# NE555_sample.net
KiCad netlist of a schematic drawn in EAGLE
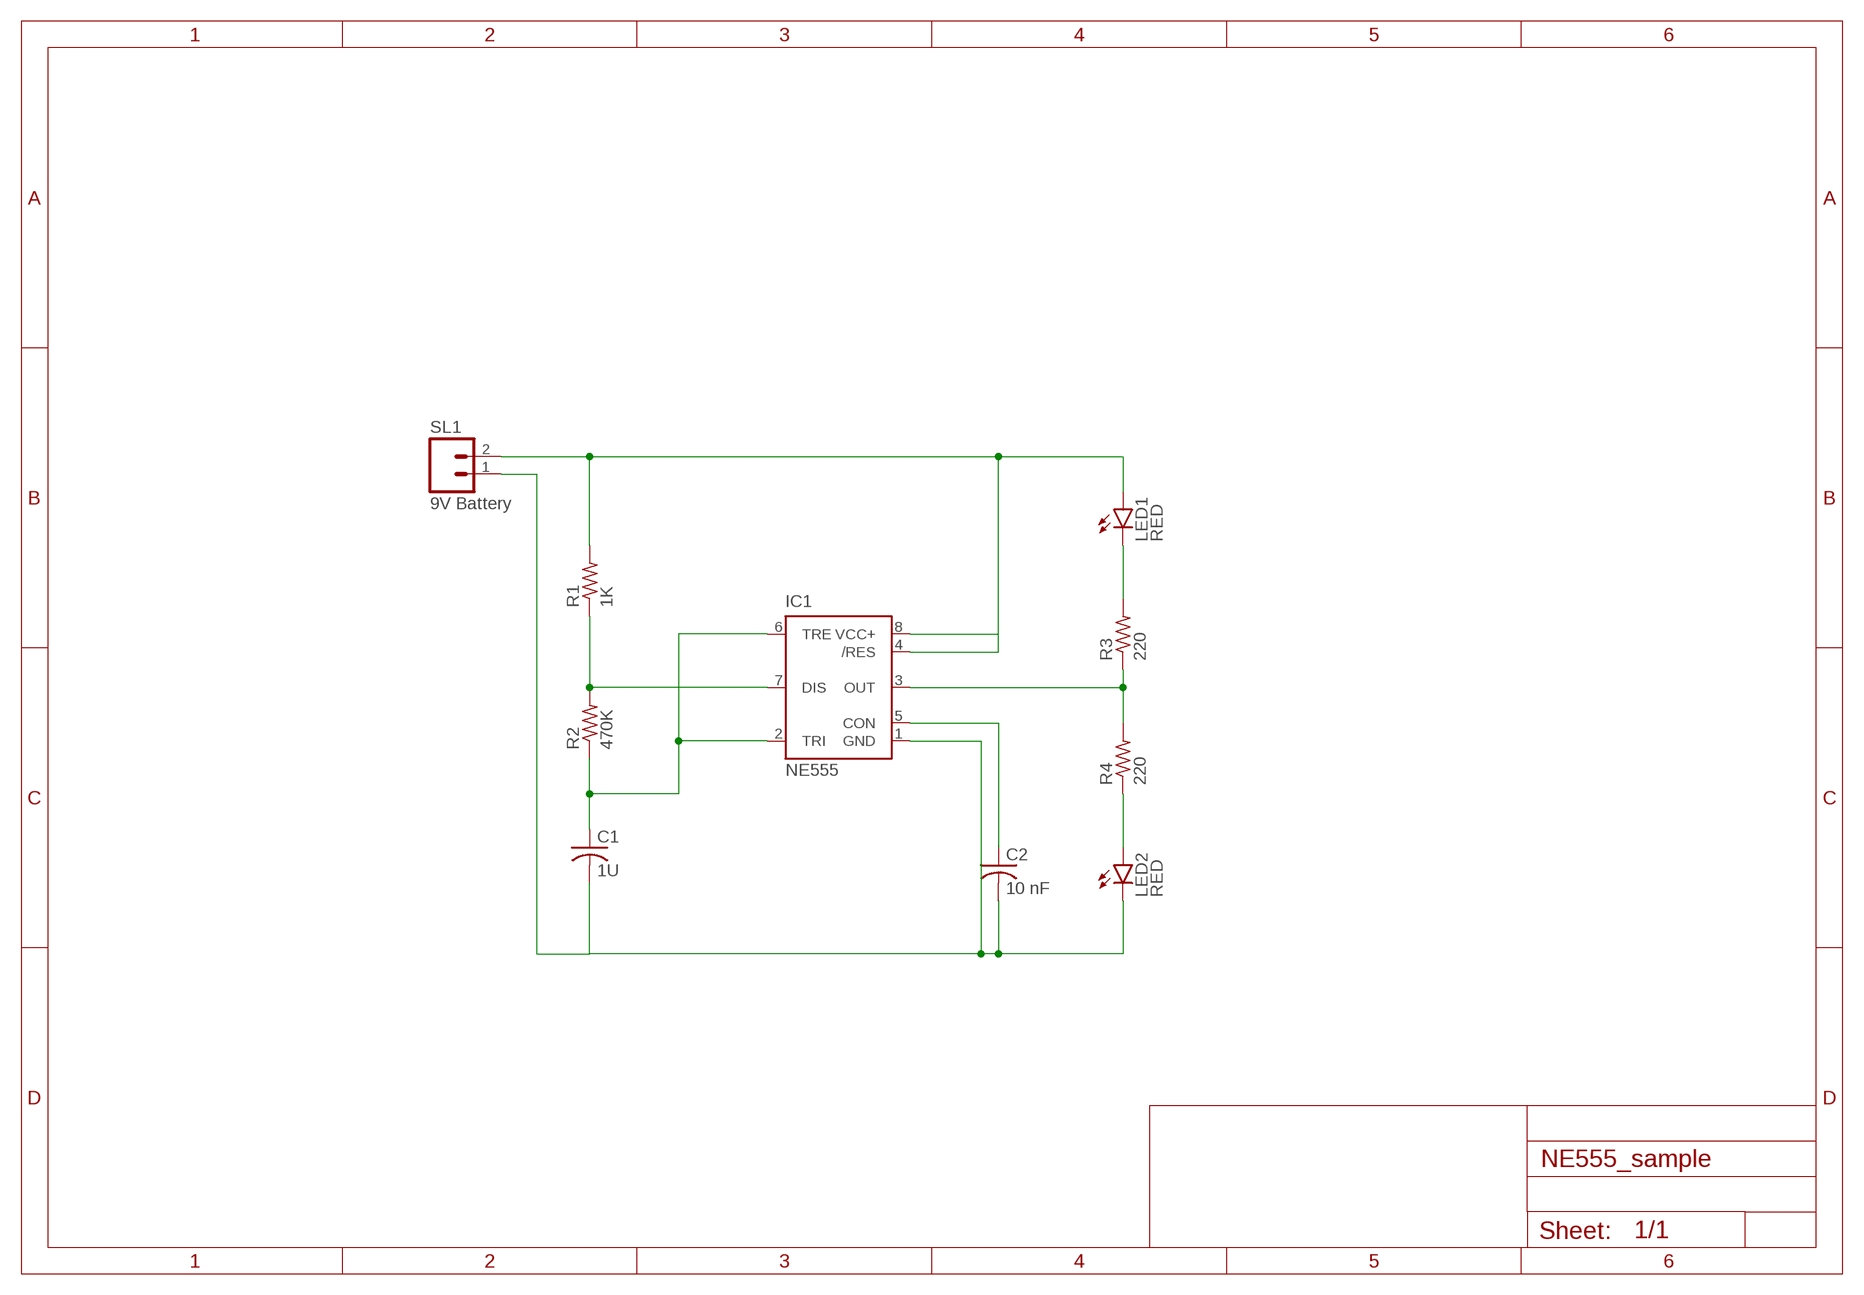
[diagram p0: schematic, sheet 1]

(export (version "E")
  (design (tool "Eeschema 10.0.6"))
  (components
    (comp (ref "C1")
      (value "1U")
      (footprint "eagle-import:C0805")
      (libsource (lib "eagle-import") (part "C-USC0805"))
    )
    (comp (ref "C2")
      (value "10 nF")
      (footprint "eagle-import:C0805")
      (libsource (lib "eagle-import") (part "C-USC0805"))
    )
    (comp (ref "IC1")
      (value "NE555")
      (footprint "eagle-import:DIL-08")
      (fields (field (name "MF") "Arrow Electronics") (field (name "MPN") "NE555N"))
      (libsource (lib "eagle-import") (part "NE555"))
    )
    (comp (ref "LED1")
      (value "RED")
      (footprint "eagle-import:CHIPLED_0805")
      (libsource (lib "eagle-import") (part "LEDCHIPLED_0805"))
    )
    (comp (ref "LED2")
      (value "RED")
      (footprint "eagle-import:CHIPLED_0805")
      (libsource (lib "eagle-import") (part "LEDCHIPLED_0805"))
    )
    (comp (ref "R1")
      (value "1K")
      (footprint "eagle-import:R0805")
      (libsource (lib "eagle-import") (part "R-US_R0805"))
    )
    (comp (ref "R2")
      (value "470K")
      (footprint "eagle-import:R0805")
      (libsource (lib "eagle-import") (part "R-US_R0805"))
    )
    (comp (ref "R3")
      (value "220")
      (footprint "eagle-import:R0805")
      (libsource (lib "eagle-import") (part "R-US_R0805"))
    )
    (comp (ref "R4")
      (value "220")
      (footprint "eagle-import:R0805")
      (libsource (lib "eagle-import") (part "R-US_R0805"))
    )
    (comp (ref "SL1")
      (value "9V Battery")
      (footprint "eagle-import:02P")
      (libsource (lib "eagle-import") (part "M02"))
    )
  )
  (nets
    (net (code "1") (name "Net-(IC1-CON)") (class "Default")
      (node (ref "C2") (pin "1") (pinfunction "1_1") (pintype "passive"))
      (node (ref "IC1") (pin "5") (pinfunction "CON_5") (pintype "input"))
    )
    (net (code "2") (name "Net-(IC1-DIS)") (class "Default")
      (node (ref "IC1") (pin "7") (pinfunction "DIS_7") (pintype "input"))
      (node (ref "R1") (pin "1") (pinfunction "1_1") (pintype "passive"))
      (node (ref "R2") (pin "2") (pinfunction "2_2") (pintype "passive"))
    )
    (net (code "3") (name "Net-(IC1-GND)") (class "Default")
      (node (ref "C1") (pin "2") (pinfunction "2_2") (pintype "passive"))
      (node (ref "C2") (pin "2") (pinfunction "2_2") (pintype "passive"))
      (node (ref "IC1") (pin "1") (pinfunction "GND_1") (pintype "power_in"))
      (node (ref "LED2") (pin "C") (pinfunction "C_C") (pintype "passive"))
      (node (ref "SL1") (pin "1") (pinfunction "1_1") (pintype "passive"))
    )
    (net (code "4") (name "Net-(IC1-OUT)") (class "Default")
      (node (ref "IC1") (pin "3") (pinfunction "OUT_3") (pintype "output"))
      (node (ref "R3") (pin "1") (pinfunction "1_1") (pintype "passive"))
      (node (ref "R4") (pin "2") (pinfunction "2_2") (pintype "passive"))
    )
    (net (code "5") (name "Net-(IC1-TRE)") (class "Default")
      (node (ref "C1") (pin "1") (pinfunction "1_1") (pintype "passive"))
      (node (ref "IC1") (pin "2") (pinfunction "TRI_2") (pintype "input"))
      (node (ref "IC1") (pin "6") (pinfunction "TRE_6") (pintype "input"))
      (node (ref "R2") (pin "1") (pinfunction "1_1") (pintype "passive"))
    )
    (net (code "6") (name "Net-(IC1-VCC+)") (class "Default")
      (node (ref "IC1") (pin "4") (pinfunction "/RES_4") (pintype "input"))
      (node (ref "IC1") (pin "8") (pinfunction "VCC+_8") (pintype "power_in"))
      (node (ref "LED1") (pin "A") (pinfunction "A_A") (pintype "passive"))
      (node (ref "R1") (pin "2") (pinfunction "2_2") (pintype "passive"))
      (node (ref "SL1") (pin "2") (pinfunction "2_2") (pintype "passive"))
    )
    (net (code "7") (name "Net-(LED1-PadC)") (class "Default")
      (node (ref "LED1") (pin "C") (pinfunction "C_C") (pintype "passive"))
      (node (ref "R3") (pin "2") (pinfunction "2_2") (pintype "passive"))
    )
    (net (code "8") (name "Net-(LED2-PadA)") (class "Default")
      (node (ref "LED2") (pin "A") (pinfunction "A_A") (pintype "passive"))
      (node (ref "R4") (pin "1") (pinfunction "1_1") (pintype "passive"))
    )
  )
)
